# Sheet4_Communications.net
KiCad netlist of a schematic drawn in Altium Designer
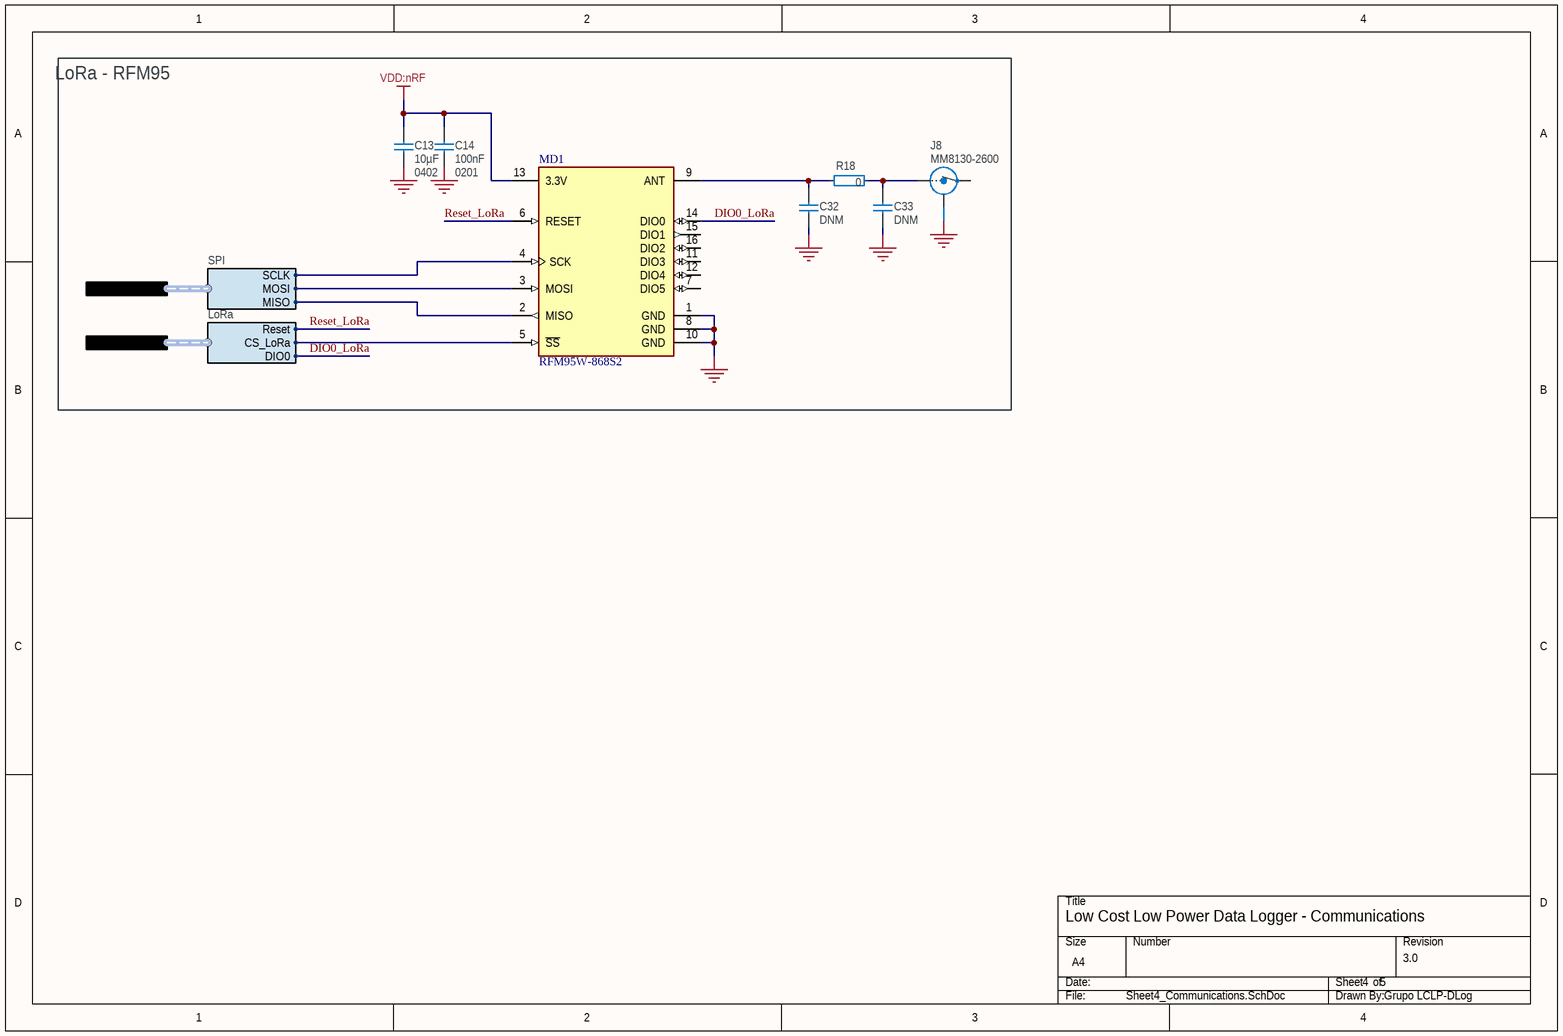
[diagram p0: Sheet4_Communications.SchDoc]

(export (version "E")
  (design (tool "Eeschema 10.0.6"))
  (components
    (comp (ref "C13")
      (value "10µF")
      (footprint "LCLP:CAPC1005X04L")
      (description "Capacitor, X6S, ±20%, 6.3V")
      (fields
        (field (name "PART NUMBER") "C0402-10µF-6.3V-X6S")
        (field (name "MANUFACTURER") "N.A.")
        (field (name "FOOTPRINT DOC") "0402")
        (field (name "AUTHOR") "getr")
      )
      (libsource (lib "") (part "CAP_1"))
    )
    (comp (ref "C14")
      (value "100nF")
      (footprint "LCLP:CAPC0603X03L_C")
      (description "Capacitor, X7R, ±10%")
      (fields
        (field (name "PART NUMBER") "C0201-100n-10V-X7R")
        (field (name "MANUFACTURER") "N.A.")
        (field (name "FOOTPRINT DOC") "0201")
        (field (name "AUTHOR") "getr")
      )
      (libsource (lib "AltiumLib") (part "CAP"))
    )
    (comp (ref "C32")
      (value "DNM")
      (footprint "LCLP:CAPC1005X04L_DNM")
      (description "Capacitor, X5R, ±10%")
      (fields
        (field (name "PART NUMBER") "C0402-2µ2-10V")
        (field (name "MANUFACTURER") "N.A.")
        (field (name "AUTHOR") "rsk")
      )
      (libsource (lib "AltiumLib") (part "CAP"))
    )
    (comp (ref "C33")
      (value "DNM")
      (footprint "LCLP:CAPC1005X04L_DNM")
      (description "Capacitor, X5R, ±10%")
      (fields
        (field (name "PART NUMBER") "C0402-2µ2-10V")
        (field (name "MANUFACTURER") "N.A.")
        (field (name "AUTHOR") "rsk")
      )
      (libsource (lib "AltiumLib") (part "CAP"))
    )
    (comp (ref "J8")
      (value "MM8130-2600")
      (footprint "LCLP:COAXIAL-SWF")
      (description "Coaxial Connector with Switch")
      (fields (field (name "MANUFACTURER") "Murata") (field (name "AUTHOR") "rsk"))
      (libsource (lib "AltiumLib") (part "Coaxial-Internal-SW"))
    )
    (comp (ref "MD1")
      (value "RFM95W-868S2")
      (footprint "FP-RFM95W-868S2-MFG")
      (description "RFM95W LoRA Transceiver Module 868MHz")
      (libsource (lib "Tiago Tavares") (part "17626aa6fba47fab2b206b7c140802e"))
    )
    (comp (ref "R18")
      (value "0")
      (footprint "LCLP:RESC1005X04L")
      (description "Resistor, ±1%, 0.05W")
      (fields
        (field (name "PART NUMBER") "R0201-1k0")
        (field (name "MANUFACTURER") "N.A.")
        (field (name "AUTHOR") "rsk")
      )
      (libsource (lib "AltiumLib") (part "RES"))
    )
  )
  (nets
    (net (code "3") (name "/CS_LoRa") (class "Default")
      (node (ref "MD1") (pin "5") (pinfunction "~{SS}_5") (pintype "input"))
    )
    (net (code "4") (name "/DIO0_LoRa") (class "Default")
      (node (ref "MD1") (pin "14") (pinfunction "DIO0_14") (pintype "bidirectional"))
    )
    (net (code "5") (name "/MISO") (class "Default")
      (node (ref "MD1") (pin "2") (pinfunction "MISO_2") (pintype "output"))
    )
    (net (code "6") (name "/MOSI") (class "Default")
      (node (ref "MD1") (pin "3") (pinfunction "MOSI_3") (pintype "input"))
    )
    (net (code "7") (name "/Reset_LoRa") (class "Default")
      (node (ref "MD1") (pin "6") (pinfunction "RESET_6") (pintype "input"))
    )
    (net (code "8") (name "/SCLK") (class "Default")
      (node (ref "MD1") (pin "4") (pinfunction "SCK_4") (pintype "input"))
    )
    (net (code "11") (name "GND") (class "Default")
      (node (ref "C13") (pin "1") (pinfunction "1_1") (pintype "passive"))
      (node (ref "C14") (pin "2") (pinfunction "2_2") (pintype "passive"))
      (node (ref "C32") (pin "1") (pinfunction "1_1") (pintype "passive"))
      (node (ref "C33") (pin "1") (pinfunction "1_1") (pintype "passive"))
      (node (ref "J8") (pin "2") (pinfunction "Shield_2") (pintype "passive"))
      (node (ref "MD1") (pin "1") (pinfunction "GND_1") (pintype "power_in"))
      (node (ref "MD1") (pin "10") (pinfunction "GND_10") (pintype "power_in"))
      (node (ref "MD1") (pin "8") (pinfunction "GND_8") (pintype "power_in"))
    )
    (net (code "12") (name "Net-(J8-IN)") (class "Default")
      (node (ref "C33") (pin "2") (pinfunction "2_2") (pintype "passive"))
      (node (ref "J8") (pin "1") (pinfunction "IN_1") (pintype "passive"))
      (node (ref "R18") (pin "1") (pinfunction "1_1") (pintype "passive"))
    )
    (net (code "13") (name "Net-(MD1-ANT)") (class "Default")
      (node (ref "C32") (pin "2") (pinfunction "2_2") (pintype "passive"))
      (node (ref "MD1") (pin "9") (pinfunction "ANT_9") (pintype "passive"))
      (node (ref "R18") (pin "2") (pinfunction "2_2") (pintype "passive"))
    )
    (net (code "14") (name "VDD:nRF") (class "Default")
      (node (ref "C13") (pin "2") (pinfunction "2_2") (pintype "passive"))
      (node (ref "C14") (pin "1") (pinfunction "1_1") (pintype "passive"))
      (node (ref "MD1") (pin "13") (pinfunction "3.3V_13") (pintype "power_in"))
    )
    (net (code "15") (name "unconnected-(J8-OUT-Pad3)") (class "Default")
      (node (ref "J8") (pin "3") (pinfunction "OUT_3") (pintype "passive"))
    )
    (net (code "16") (name "unconnected-(MD1-DIO1-Pad15)") (class "Default")
      (node (ref "MD1") (pin "15") (pinfunction "DIO1_15") (pintype "output"))
    )
    (net (code "17") (name "unconnected-(MD1-DIO2-Pad16)") (class "Default")
      (node (ref "MD1") (pin "16") (pinfunction "DIO2_16") (pintype "bidirectional"))
    )
    (net (code "18") (name "unconnected-(MD1-DIO3-Pad11)") (class "Default")
      (node (ref "MD1") (pin "11") (pinfunction "DIO3_11") (pintype "bidirectional"))
    )
    (net (code "19") (name "unconnected-(MD1-DIO4-Pad12)") (class "Default")
      (node (ref "MD1") (pin "12") (pinfunction "DIO4_12") (pintype "bidirectional"))
    )
    (net (code "20") (name "unconnected-(MD1-DIO5-Pad7)") (class "Default")
      (node (ref "MD1") (pin "7") (pinfunction "DIO5_7") (pintype "bidirectional"))
    )
  )
)
